# Carte_m_re.net
KiCad netlist of a schematic drawn in EAGLE
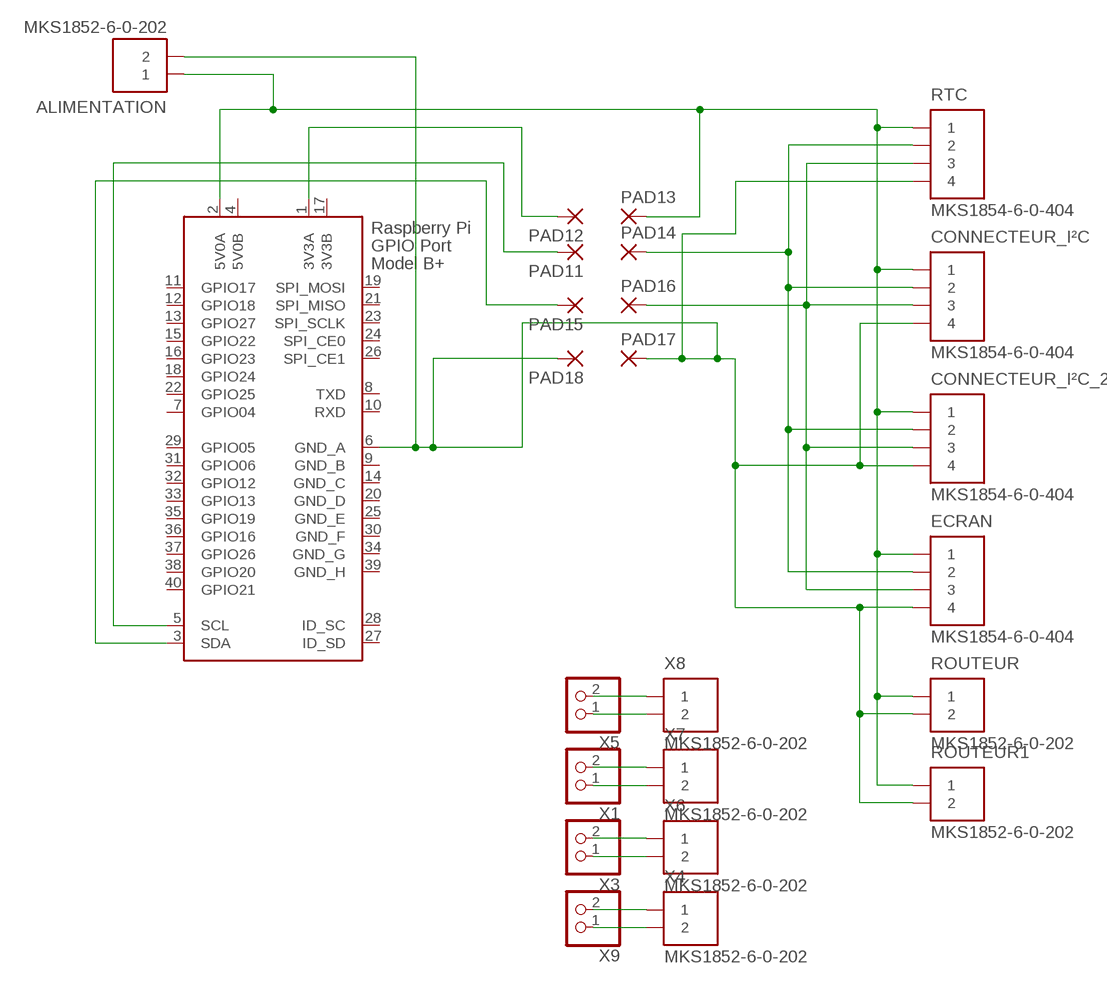
[diagram p0: schematic, sheet 1]

(export (version "E")
  (design (tool "Eeschema 10.0.6"))
  (components
    (comp (ref "ALIMENTATION")
      (value "MKS1852-6-0-202")
      (footprint "eagle-import:MKS1852-6-0-202")
      (libsource (lib "eagle-import") (part "MKS1852-6-0-202"))
    )
    (comp (ref "CONNECTEUR_I²C")
      (value "MKS1854-6-0-404")
      (footprint "eagle-import:MKS1854-6-0-404")
      (libsource (lib "eagle-import") (part "MKS1854-6-0-404"))
    )
    (comp (ref "CONNECTEUR_I²C_2")
      (value "MKS1854-6-0-404")
      (footprint "eagle-import:MKS1854-6-0-404")
      (libsource (lib "eagle-import") (part "MKS1854-6-0-404"))
    )
    (comp (ref "ECRAN")
      (value "MKS1854-6-0-404")
      (footprint "eagle-import:MKS1854-6-0-404")
      (libsource (lib "eagle-import") (part "MKS1854-6-0-404"))
    )
    (comp (ref "PAD11")
      (value "1,6/0,9")
      (footprint "eagle-import:1,6_0,9")
      (libsource (lib "eagle-import") (part "1,6/0,9"))
    )
    (comp (ref "PAD12")
      (value "1,6/0,9")
      (footprint "eagle-import:1,6_0,9")
      (libsource (lib "eagle-import") (part "1,6/0,9"))
    )
    (comp (ref "PAD13")
      (value "1,6/0,9")
      (footprint "eagle-import:1,6_0,9")
      (libsource (lib "eagle-import") (part "1,6/0,9"))
    )
    (comp (ref "PAD14")
      (value "1,6/0,9")
      (footprint "eagle-import:1,6_0,9")
      (libsource (lib "eagle-import") (part "1,6/0,9"))
    )
    (comp (ref "PAD15")
      (value "1,6/0,9")
      (footprint "eagle-import:1,6_0,9")
      (libsource (lib "eagle-import") (part "1,6/0,9"))
    )
    (comp (ref "PAD16")
      (value "1,6/0,9")
      (footprint "eagle-import:1,6_0,9")
      (libsource (lib "eagle-import") (part "1,6/0,9"))
    )
    (comp (ref "PAD17")
      (value "1,6/0,9")
      (footprint "eagle-import:1,6_0,9")
      (libsource (lib "eagle-import") (part "1,6/0,9"))
    )
    (comp (ref "PAD18")
      (value "1,6/0,9")
      (footprint "eagle-import:1,6_0,9")
      (libsource (lib "eagle-import") (part "1,6/0,9"))
    )
    (comp (ref "ROUTEUR")
      (value "MKS1852-6-0-202")
      (footprint "eagle-import:MKS1852-6-0-202")
      (libsource (lib "eagle-import") (part "MKS1852-6-0-202"))
    )
    (comp (ref "ROUTEUR1")
      (value "MKS1852-6-0-202")
      (footprint "eagle-import:MKS1852-6-0-202")
      (libsource (lib "eagle-import") (part "MKS1852-6-0-202"))
    )
    (comp (ref "RTC")
      (value "MKS1854-6-0-404")
      (footprint "eagle-import:MKS1854-6-0-404")
      (libsource (lib "eagle-import") (part "MKS1854-6-0-404"))
    )
    (comp (ref "X1")
      (value "PINHD-1X2")
      (footprint "eagle-import:1X02")
      (libsource (lib "eagle-import") (part "PINHD-1X2"))
    )
    (comp (ref "X2")
      (value "RASPI_GPIO_B+#_PIN")
      (footprint "eagle-import:RASPI_GPIO_B+_PIN")
      (libsource (lib "eagle-import") (part "RASPI_GPIO_B+#_PIN"))
    )
    (comp (ref "X3")
      (value "PINHD-1X2")
      (footprint "eagle-import:1X02")
      (libsource (lib "eagle-import") (part "PINHD-1X2"))
    )
    (comp (ref "X4")
      (value "MKS1852-6-0-202")
      (footprint "eagle-import:MKS1852-6-0-202")
      (libsource (lib "eagle-import") (part "MKS1852-6-0-202"))
    )
    (comp (ref "X5")
      (value "PINHD-1X2")
      (footprint "eagle-import:1X02")
      (libsource (lib "eagle-import") (part "PINHD-1X2"))
    )
    (comp (ref "X6")
      (value "MKS1852-6-0-202")
      (footprint "eagle-import:MKS1852-6-0-202")
      (libsource (lib "eagle-import") (part "MKS1852-6-0-202"))
    )
    (comp (ref "X7")
      (value "MKS1852-6-0-202")
      (footprint "eagle-import:MKS1852-6-0-202")
      (libsource (lib "eagle-import") (part "MKS1852-6-0-202"))
    )
    (comp (ref "X8")
      (value "MKS1852-6-0-202")
      (footprint "eagle-import:MKS1852-6-0-202")
      (libsource (lib "eagle-import") (part "MKS1852-6-0-202"))
    )
    (comp (ref "X9")
      (value "PINHD-1X2")
      (footprint "eagle-import:1X02")
      (libsource (lib "eagle-import") (part "PINHD-1X2"))
    )
  )
  (nets
    (net (code "1") (name "/3V3B") (class "Default")
      (node (ref "X2") (pin "17") (pinfunction "3V3B_17") (pintype "power_in"))
    )
    (net (code "2") (name "/5V0B") (class "Default")
      (node (ref "X2") (pin "4") (pinfunction "5V0B_4") (pintype "power_in"))
    )
    (net (code "3") (name "/GND_B") (class "Default")
      (node (ref "X2") (pin "9") (pinfunction "GND_B_9") (pintype "power_in"))
    )
    (net (code "4") (name "/GND_C") (class "Default")
      (node (ref "X2") (pin "14") (pinfunction "GND_C_14") (pintype "power_in"))
    )
    (net (code "5") (name "/GND_D") (class "Default")
      (node (ref "X2") (pin "20") (pinfunction "GND_D_20") (pintype "power_in"))
    )
    (net (code "6") (name "/GND_E") (class "Default")
      (node (ref "X2") (pin "25") (pinfunction "GND_E_25") (pintype "power_in"))
    )
    (net (code "7") (name "/GND_F") (class "Default")
      (node (ref "X2") (pin "30") (pinfunction "GND_F_30") (pintype "power_in"))
    )
    (net (code "8") (name "/GND_G") (class "Default")
      (node (ref "X2") (pin "34") (pinfunction "GND_G_34") (pintype "power_in"))
    )
    (net (code "9") (name "/GND_H") (class "Default")
      (node (ref "X2") (pin "39") (pinfunction "GND_H_39") (pintype "power_in"))
    )
    (net (code "10") (name "Net-(PAD11-P)") (class "Default")
      (node (ref "PAD11") (pin "1") (pinfunction "P_1") (pintype "passive"))
      (node (ref "X2") (pin "5") (pinfunction "SCL_5") (pintype "bidirectional"))
    )
    (net (code "11") (name "Net-(PAD12-P)") (class "Default")
      (node (ref "PAD12") (pin "1") (pinfunction "P_1") (pintype "passive"))
      (node (ref "X2") (pin "1") (pinfunction "3V3A_1") (pintype "power_in"))
    )
    (net (code "12") (name "Net-(PAD13-P)") (class "Default")
      (node (ref "ALIMENTATION") (pin "1") (pinfunction "1_1") (pintype "input"))
      (node (ref "CONNECTEUR_I²C") (pin "1") (pinfunction "1_1") (pintype "input"))
      (node (ref "CONNECTEUR_I²C_2") (pin "1") (pinfunction "1_1") (pintype "input"))
      (node (ref "ECRAN") (pin "1") (pinfunction "1_1") (pintype "input"))
      (node (ref "PAD13") (pin "1") (pinfunction "P_1") (pintype "passive"))
      (node (ref "ROUTEUR") (pin "1") (pinfunction "1_1") (pintype "input"))
      (node (ref "ROUTEUR1") (pin "1") (pinfunction "1_1") (pintype "input"))
      (node (ref "RTC") (pin "1") (pinfunction "1_1") (pintype "input"))
      (node (ref "X2") (pin "2") (pinfunction "5V0A_2") (pintype "power_in"))
    )
    (net (code "13") (name "Net-(PAD14-P)") (class "Default")
      (node (ref "CONNECTEUR_I²C") (pin "2") (pinfunction "2_2") (pintype "input"))
      (node (ref "CONNECTEUR_I²C_2") (pin "2") (pinfunction "2_2") (pintype "input"))
      (node (ref "ECRAN") (pin "2") (pinfunction "2_2") (pintype "input"))
      (node (ref "PAD14") (pin "1") (pinfunction "P_1") (pintype "passive"))
      (node (ref "RTC") (pin "2") (pinfunction "2_2") (pintype "input"))
    )
    (net (code "14") (name "Net-(PAD15-P)") (class "Default")
      (node (ref "PAD15") (pin "1") (pinfunction "P_1") (pintype "passive"))
      (node (ref "X2") (pin "3") (pinfunction "SDA_3") (pintype "bidirectional"))
    )
    (net (code "15") (name "Net-(PAD16-P)") (class "Default")
      (node (ref "CONNECTEUR_I²C") (pin "3") (pinfunction "3_3") (pintype "input"))
      (node (ref "CONNECTEUR_I²C_2") (pin "3") (pinfunction "3_3") (pintype "input"))
      (node (ref "ECRAN") (pin "3") (pinfunction "3_3") (pintype "input"))
      (node (ref "PAD16") (pin "1") (pinfunction "P_1") (pintype "passive"))
      (node (ref "RTC") (pin "3") (pinfunction "3_3") (pintype "input"))
    )
    (net (code "16") (name "Net-(PAD17-P)") (class "Default")
      (node (ref "ALIMENTATION") (pin "2") (pinfunction "2_2") (pintype "input"))
      (node (ref "CONNECTEUR_I²C") (pin "4") (pinfunction "4_4") (pintype "input"))
      (node (ref "CONNECTEUR_I²C_2") (pin "4") (pinfunction "4_4") (pintype "input"))
      (node (ref "ECRAN") (pin "4") (pinfunction "4_4") (pintype "input"))
      (node (ref "PAD17") (pin "1") (pinfunction "P_1") (pintype "passive"))
      (node (ref "PAD18") (pin "1") (pinfunction "P_1") (pintype "passive"))
      (node (ref "ROUTEUR") (pin "2") (pinfunction "2_2") (pintype "input"))
      (node (ref "ROUTEUR1") (pin "2") (pinfunction "2_2") (pintype "input"))
      (node (ref "RTC") (pin "4") (pinfunction "4_4") (pintype "input"))
      (node (ref "X2") (pin "6") (pinfunction "GND_A_6") (pintype "power_in"))
    )
    (net (code "17") (name "Net-(X1-Pad1)") (class "Default")
      (node (ref "X1") (pin "1") (pinfunction "1_1") (pintype "passive"))
      (node (ref "X7") (pin "2") (pinfunction "2_2") (pintype "input"))
    )
    (net (code "18") (name "Net-(X1-Pad2)") (class "Default")
      (node (ref "X1") (pin "2") (pinfunction "2_2") (pintype "passive"))
      (node (ref "X7") (pin "1") (pinfunction "1_1") (pintype "input"))
    )
    (net (code "19") (name "Net-(X3-Pad1)") (class "Default")
      (node (ref "X3") (pin "1") (pinfunction "1_1") (pintype "passive"))
      (node (ref "X6") (pin "2") (pinfunction "2_2") (pintype "input"))
    )
    (net (code "20") (name "Net-(X3-Pad2)") (class "Default")
      (node (ref "X3") (pin "2") (pinfunction "2_2") (pintype "passive"))
      (node (ref "X6") (pin "1") (pinfunction "1_1") (pintype "input"))
    )
    (net (code "21") (name "Net-(X4-Pad1)") (class "Default")
      (node (ref "X4") (pin "1") (pinfunction "1_1") (pintype "input"))
      (node (ref "X9") (pin "2") (pinfunction "2_2") (pintype "passive"))
    )
    (net (code "22") (name "Net-(X4-Pad2)") (class "Default")
      (node (ref "X4") (pin "2") (pinfunction "2_2") (pintype "input"))
      (node (ref "X9") (pin "1") (pinfunction "1_1") (pintype "passive"))
    )
    (net (code "23") (name "Net-(X5-Pad1)") (class "Default")
      (node (ref "X5") (pin "1") (pinfunction "1_1") (pintype "passive"))
      (node (ref "X8") (pin "2") (pinfunction "2_2") (pintype "input"))
    )
    (net (code "24") (name "Net-(X5-Pad2)") (class "Default")
      (node (ref "X5") (pin "2") (pinfunction "2_2") (pintype "passive"))
      (node (ref "X8") (pin "1") (pinfunction "1_1") (pintype "input"))
    )
    (net (code "25") (name "unconnected-(X2-GPIO04-Pad7)") (class "Default")
      (node (ref "X2") (pin "7") (pinfunction "GPIO04_7") (pintype "bidirectional"))
    )
    (net (code "26") (name "unconnected-(X2-GPIO05-Pad29)") (class "Default")
      (node (ref "X2") (pin "29") (pinfunction "GPIO05_29") (pintype "no_connect"))
    )
    (net (code "27") (name "unconnected-(X2-GPIO06-Pad31)") (class "Default")
      (node (ref "X2") (pin "31") (pinfunction "GPIO06_31") (pintype "no_connect"))
    )
    (net (code "28") (name "unconnected-(X2-GPIO12-Pad32)") (class "Default")
      (node (ref "X2") (pin "32") (pinfunction "GPIO12_32") (pintype "no_connect"))
    )
    (net (code "29") (name "unconnected-(X2-GPIO13-Pad33)") (class "Default")
      (node (ref "X2") (pin "33") (pinfunction "GPIO13_33") (pintype "no_connect"))
    )
    (net (code "30") (name "unconnected-(X2-GPIO16-Pad36)") (class "Default")
      (node (ref "X2") (pin "36") (pinfunction "GPIO16_36") (pintype "no_connect"))
    )
    (net (code "31") (name "unconnected-(X2-GPIO17-Pad11)") (class "Default")
      (node (ref "X2") (pin "11") (pinfunction "GPIO17_11") (pintype "bidirectional"))
    )
    (net (code "32") (name "unconnected-(X2-GPIO18-Pad12)") (class "Default")
      (node (ref "X2") (pin "12") (pinfunction "GPIO18_12") (pintype "bidirectional"))
    )
    (net (code "33") (name "unconnected-(X2-GPIO19-Pad35)") (class "Default")
      (node (ref "X2") (pin "35") (pinfunction "GPIO19_35") (pintype "no_connect"))
    )
    (net (code "34") (name "unconnected-(X2-GPIO20-Pad38)") (class "Default")
      (node (ref "X2") (pin "38") (pinfunction "GPIO20_38") (pintype "no_connect"))
    )
    (net (code "35") (name "unconnected-(X2-GPIO21-Pad40)") (class "Default")
      (node (ref "X2") (pin "40") (pinfunction "GPIO21_40") (pintype "no_connect"))
    )
    (net (code "36") (name "unconnected-(X2-GPIO22-Pad15)") (class "Default")
      (node (ref "X2") (pin "15") (pinfunction "GPIO22_15") (pintype "bidirectional"))
    )
    (net (code "37") (name "unconnected-(X2-GPIO23-Pad16)") (class "Default")
      (node (ref "X2") (pin "16") (pinfunction "GPIO23_16") (pintype "bidirectional"))
    )
    (net (code "38") (name "unconnected-(X2-GPIO24-Pad18)") (class "Default")
      (node (ref "X2") (pin "18") (pinfunction "GPIO24_18") (pintype "bidirectional"))
    )
    (net (code "39") (name "unconnected-(X2-GPIO25-Pad22)") (class "Default")
      (node (ref "X2") (pin "22") (pinfunction "GPIO25_22") (pintype "bidirectional"))
    )
    (net (code "40") (name "unconnected-(X2-GPIO26-Pad37)") (class "Default")
      (node (ref "X2") (pin "37") (pinfunction "GPIO26_37") (pintype "no_connect"))
    )
    (net (code "41") (name "unconnected-(X2-GPIO27-Pad13)") (class "Default")
      (node (ref "X2") (pin "13") (pinfunction "GPIO27_13") (pintype "bidirectional"))
    )
    (net (code "42") (name "unconnected-(X2-ID_SC-Pad28)") (class "Default")
      (node (ref "X2") (pin "28") (pinfunction "ID_SC_28") (pintype "no_connect"))
    )
    (net (code "43") (name "unconnected-(X2-ID_SD-Pad27)") (class "Default")
      (node (ref "X2") (pin "27") (pinfunction "ID_SD_27") (pintype "no_connect"))
    )
    (net (code "44") (name "unconnected-(X2-RXD-Pad10)") (class "Default")
      (node (ref "X2") (pin "10") (pinfunction "RXD_10") (pintype "bidirectional"))
    )
    (net (code "45") (name "unconnected-(X2-SPI_CE0-Pad24)") (class "Default")
      (node (ref "X2") (pin "24") (pinfunction "SPI_CE0_24") (pintype "bidirectional"))
    )
    (net (code "46") (name "unconnected-(X2-SPI_CE1-Pad26)") (class "Default")
      (node (ref "X2") (pin "26") (pinfunction "SPI_CE1_26") (pintype "bidirectional"))
    )
    (net (code "47") (name "unconnected-(X2-SPI_MISO-Pad21)") (class "Default")
      (node (ref "X2") (pin "21") (pinfunction "SPI_MISO_21") (pintype "bidirectional"))
    )
    (net (code "48") (name "unconnected-(X2-SPI_MOSI-Pad19)") (class "Default")
      (node (ref "X2") (pin "19") (pinfunction "SPI_MOSI_19") (pintype "bidirectional"))
    )
    (net (code "49") (name "unconnected-(X2-SPI_SCLK-Pad23)") (class "Default")
      (node (ref "X2") (pin "23") (pinfunction "SPI_SCLK_23") (pintype "bidirectional"))
    )
    (net (code "50") (name "unconnected-(X2-TXD-Pad8)") (class "Default")
      (node (ref "X2") (pin "8") (pinfunction "TXD_8") (pintype "bidirectional"))
    )
  )
)
